# KimCard-r5.net
KiCad netlist of a schematic drawn in EAGLE
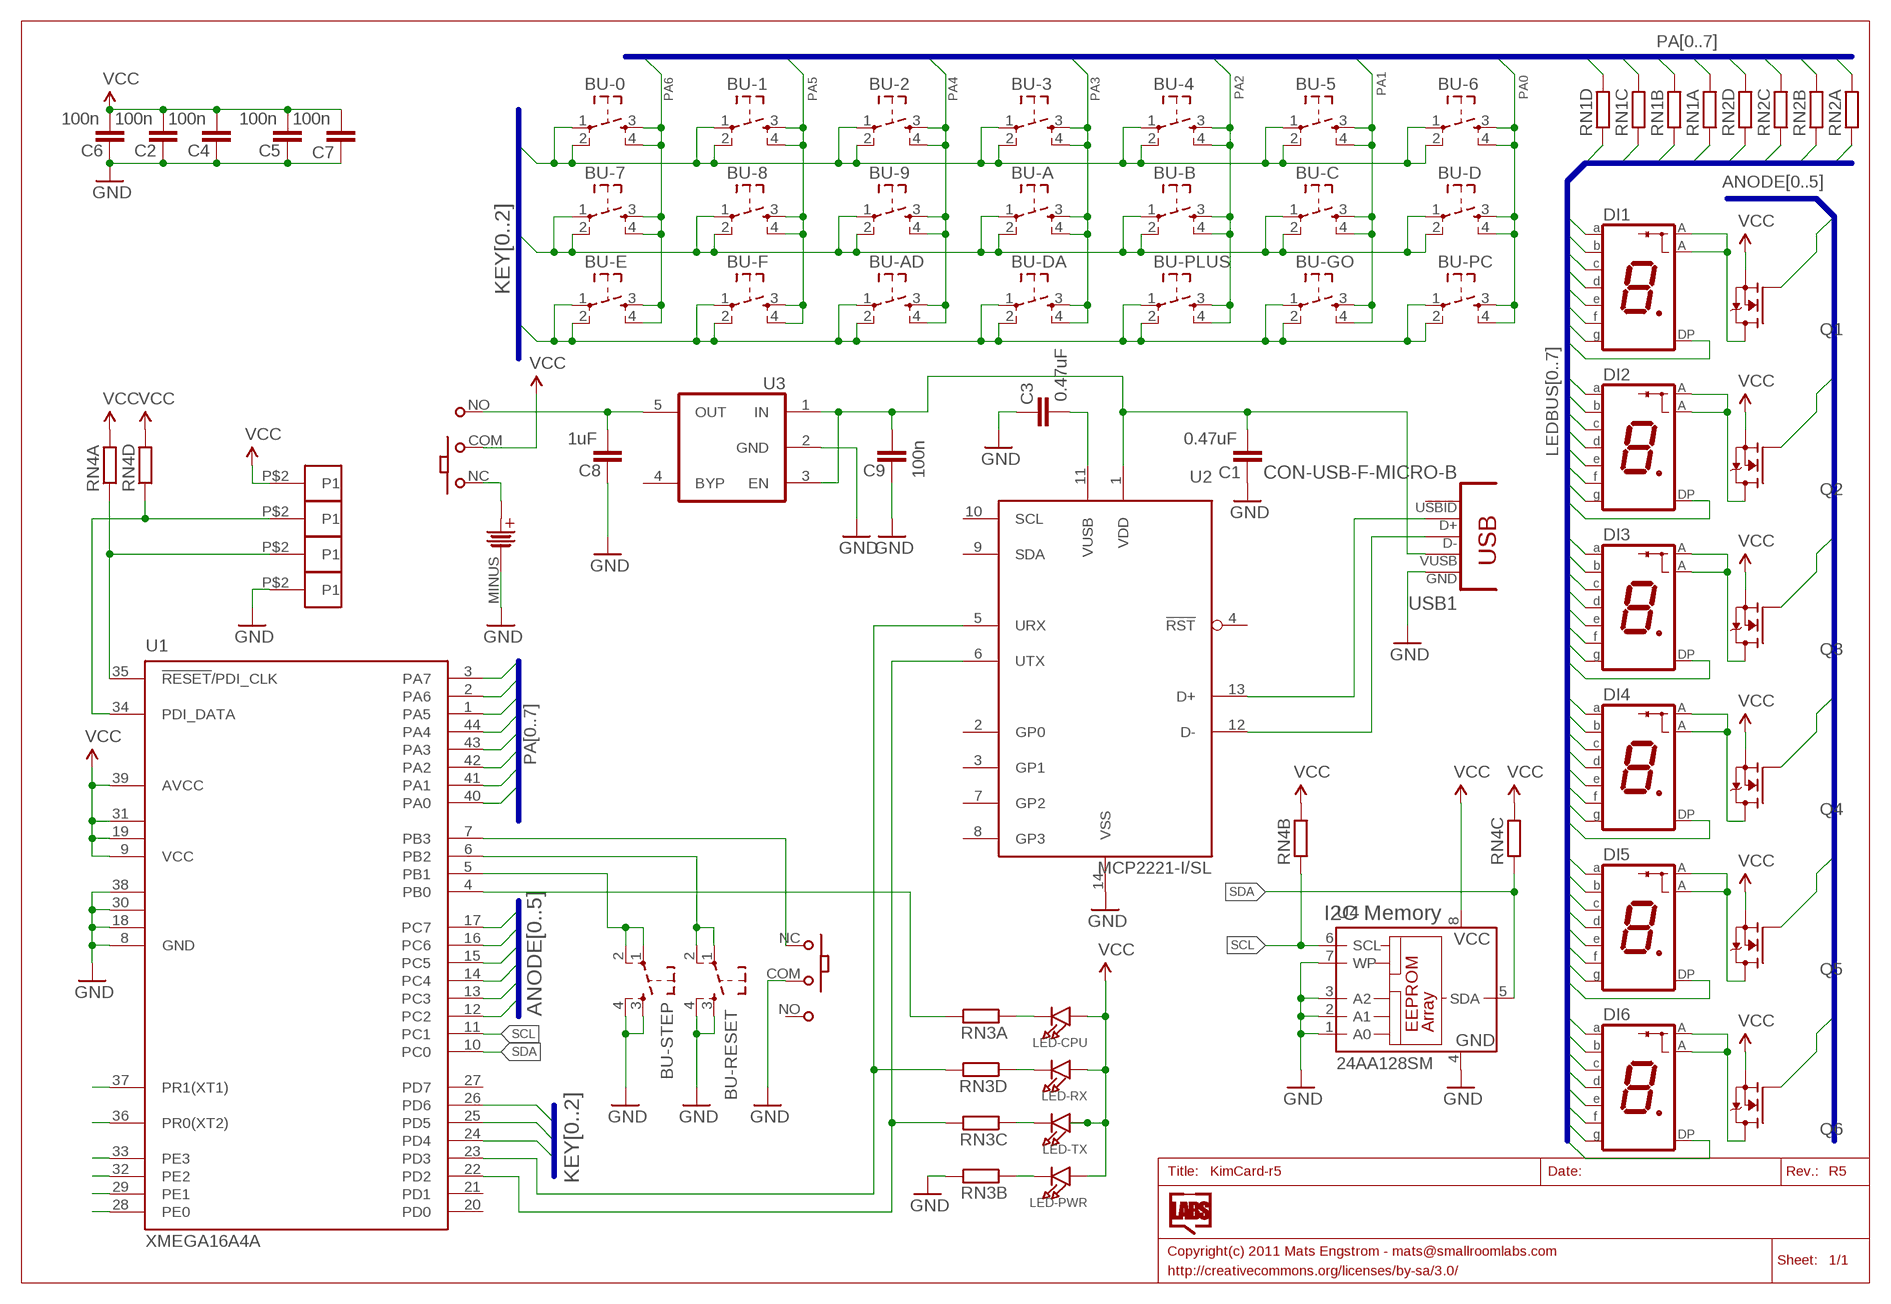
[diagram p0: schematic, sheet 1]

(export (version "E")
  (design (tool "Eeschema 10.0.6"))
  (components
    (comp (ref "BA1")
      (value "BATTERY-3V")
      (footprint "eagle-import:AAAX2")
      (libsource (lib "eagle-import") (part "BATTERY-3V"))
    )
    (comp (ref "BU-0")
      (value "SW_TACT_4P")
      (footprint "eagle-import:SW_TACT_SMALL")
      (libsource (lib "eagle-import") (part "SW_TACT_4P"))
    )
    (comp (ref "BU-1")
      (value "SW_TACT_4P")
      (footprint "eagle-import:SW_TACT_SMALL")
      (libsource (lib "eagle-import") (part "SW_TACT_4P"))
    )
    (comp (ref "BU-2")
      (value "SW_TACT_4P")
      (footprint "eagle-import:SW_TACT_SMALL")
      (libsource (lib "eagle-import") (part "SW_TACT_4P"))
    )
    (comp (ref "BU-3")
      (value "SW_TACT_4P")
      (footprint "eagle-import:SW_TACT_SMALL")
      (libsource (lib "eagle-import") (part "SW_TACT_4P"))
    )
    (comp (ref "BU-4")
      (value "SW_TACT_4P")
      (footprint "eagle-import:SW_TACT_SMALL")
      (libsource (lib "eagle-import") (part "SW_TACT_4P"))
    )
    (comp (ref "BU-5")
      (value "SW_TACT_4P")
      (footprint "eagle-import:SW_TACT_SMALL")
      (libsource (lib "eagle-import") (part "SW_TACT_4P"))
    )
    (comp (ref "BU-6")
      (value "SW_TACT_4P")
      (footprint "eagle-import:SW_TACT_SMALL")
      (libsource (lib "eagle-import") (part "SW_TACT_4P"))
    )
    (comp (ref "BU-7")
      (value "SW_TACT_4P")
      (footprint "eagle-import:SW_TACT_SMALL")
      (libsource (lib "eagle-import") (part "SW_TACT_4P"))
    )
    (comp (ref "BU-8")
      (value "SW_TACT_4P")
      (footprint "eagle-import:SW_TACT_SMALL")
      (libsource (lib "eagle-import") (part "SW_TACT_4P"))
    )
    (comp (ref "BU-9")
      (value "SW_TACT_4P")
      (footprint "eagle-import:SW_TACT_SMALL")
      (libsource (lib "eagle-import") (part "SW_TACT_4P"))
    )
    (comp (ref "BU-A")
      (value "SW_TACT_4P")
      (footprint "eagle-import:SW_TACT_SMALL")
      (libsource (lib "eagle-import") (part "SW_TACT_4P"))
    )
    (comp (ref "BU-AD")
      (value "SW_TACT_4P")
      (footprint "eagle-import:SW_TACT_SMALL")
      (libsource (lib "eagle-import") (part "SW_TACT_4P"))
    )
    (comp (ref "BU-B")
      (value "SW_TACT_4P")
      (footprint "eagle-import:SW_TACT_SMALL")
      (libsource (lib "eagle-import") (part "SW_TACT_4P"))
    )
    (comp (ref "BU-C")
      (value "SW_TACT_4P")
      (footprint "eagle-import:SW_TACT_SMALL")
      (libsource (lib "eagle-import") (part "SW_TACT_4P"))
    )
    (comp (ref "BU-D")
      (value "SW_TACT_4P")
      (footprint "eagle-import:SW_TACT_SMALL")
      (libsource (lib "eagle-import") (part "SW_TACT_4P"))
    )
    (comp (ref "BU-DA")
      (value "SW_TACT_4P")
      (footprint "eagle-import:SW_TACT_SMALL")
      (libsource (lib "eagle-import") (part "SW_TACT_4P"))
    )
    (comp (ref "BU-E")
      (value "SW_TACT_4P")
      (footprint "eagle-import:SW_TACT_SMALL")
      (libsource (lib "eagle-import") (part "SW_TACT_4P"))
    )
    (comp (ref "BU-F")
      (value "SW_TACT_4P")
      (footprint "eagle-import:SW_TACT_SMALL")
      (libsource (lib "eagle-import") (part "SW_TACT_4P"))
    )
    (comp (ref "BU-GO")
      (value "SW_TACT_4P")
      (footprint "eagle-import:SW_TACT_SMALL")
      (libsource (lib "eagle-import") (part "SW_TACT_4P"))
    )
    (comp (ref "BU-PC")
      (value "SW_TACT_4P")
      (footprint "eagle-import:SW_TACT_SMALL")
      (libsource (lib "eagle-import") (part "SW_TACT_4P"))
    )
    (comp (ref "BU-PLUS")
      (value "SW_TACT_4P")
      (footprint "eagle-import:SW_TACT_SMALL")
      (libsource (lib "eagle-import") (part "SW_TACT_4P"))
    )
    (comp (ref "BU-RESET")
      (value "SW_TACT_4P")
      (footprint "eagle-import:SW_TACT_SMALL")
      (libsource (lib "eagle-import") (part "SW_TACT_4P"))
    )
    (comp (ref "BU-STEP")
      (value "SW_TACT_4P")
      (footprint "eagle-import:SW_TACT_SMALL")
      (libsource (lib "eagle-import") (part "SW_TACT_4P"))
    )
    (comp (ref "C1")
      (value "0.47uF")
      (footprint "eagle-import:0805")
      (libsource (lib "eagle-import") (part "CAP0805"))
    )
    (comp (ref "C2")
      (value "100n")
      (footprint "eagle-import:0805")
      (libsource (lib "eagle-import") (part "CAP0805"))
    )
    (comp (ref "C3")
      (value "0.47uF")
      (footprint "eagle-import:0805")
      (libsource (lib "eagle-import") (part "CAP0805"))
    )
    (comp (ref "C4")
      (value "100n")
      (footprint "eagle-import:0805")
      (libsource (lib "eagle-import") (part "CAP0805"))
    )
    (comp (ref "C5")
      (value "100n")
      (footprint "eagle-import:0805")
      (libsource (lib "eagle-import") (part "CAP0805"))
    )
    (comp (ref "C6")
      (value "100n")
      (footprint "eagle-import:0805")
      (libsource (lib "eagle-import") (part "CAP0805"))
    )
    (comp (ref "C7")
      (value "100n")
      (footprint "eagle-import:0805")
      (libsource (lib "eagle-import") (part "CAP0805"))
    )
    (comp (ref "C8")
      (value "1uF")
      (footprint "eagle-import:0805")
      (libsource (lib "eagle-import") (part "CAP0805"))
    )
    (comp (ref "C9")
      (value "100n")
      (footprint "eagle-import:0805")
      (libsource (lib "eagle-import") (part "CAP0805"))
    )
    (comp (ref "DI1")
      (value "7SEG-CA2")
      (footprint "eagle-import:KCSA03")
      (libsource (lib "eagle-import") (part "7SEG-CA2"))
    )
    (comp (ref "DI2")
      (value "7SEG-CA2")
      (footprint "eagle-import:KCSA03")
      (libsource (lib "eagle-import") (part "7SEG-CA2"))
    )
    (comp (ref "DI3")
      (value "7SEG-CA2")
      (footprint "eagle-import:KCSA03")
      (libsource (lib "eagle-import") (part "7SEG-CA2"))
    )
    (comp (ref "DI4")
      (value "7SEG-CA2")
      (footprint "eagle-import:KCSA03")
      (libsource (lib "eagle-import") (part "7SEG-CA2"))
    )
    (comp (ref "DI5")
      (value "7SEG-CA2")
      (footprint "eagle-import:KCSA03")
      (libsource (lib "eagle-import") (part "7SEG-CA2"))
    )
    (comp (ref "DI6")
      (value "7SEG-CA2")
      (footprint "eagle-import:KCSA03")
      (libsource (lib "eagle-import") (part "7SEG-CA2"))
    )
    (comp (ref "LED-CPU")
      (value "LEDSMD0805")
      (footprint "eagle-import:CHIPLED_0805")
      (libsource (lib "eagle-import") (part "LEDSMD0805"))
    )
    (comp (ref "LED-PWR")
      (value "LEDSMD0805")
      (footprint "eagle-import:CHIPLED_0805")
      (libsource (lib "eagle-import") (part "LEDSMD0805"))
    )
    (comp (ref "LED-RX")
      (value "LEDSMD0805")
      (footprint "eagle-import:CHIPLED_0805")
      (libsource (lib "eagle-import") (part "LEDSMD0805"))
    )
    (comp (ref "LED-TX")
      (value "LEDSMD0805")
      (footprint "eagle-import:CHIPLED_0805")
      (libsource (lib "eagle-import") (part "LEDSMD0805"))
    )
    (comp (ref "PDI-CLK")
      (value "PAD-2X3")
      (footprint "eagle-import:PAD2X3")
      (libsource (lib "eagle-import") (part "PAD-2X3"))
    )
    (comp (ref "PDI-DATA")
      (value "PAD-2X3")
      (footprint "eagle-import:PAD2X3")
      (libsource (lib "eagle-import") (part "PAD-2X3"))
    )
    (comp (ref "PDI-GND")
      (value "PAD-2X3")
      (footprint "eagle-import:PAD2X3")
      (libsource (lib "eagle-import") (part "PAD-2X3"))
    )
    (comp (ref "PDI-VCC")
      (value "PAD-2X3")
      (footprint "eagle-import:PAD2X3")
      (libsource (lib "eagle-import") (part "PAD-2X3"))
    )
    (comp (ref "Q1")
      (value "TRANSISTOR_FET_BS170-SOT-23")
      (footprint "eagle-import:SOT-23")
      (libsource (lib "eagle-import") (part "TRANSISTOR_FET_BS170-SOT-23"))
    )
    (comp (ref "Q2")
      (value "TRANSISTOR_FET_BS170-SOT-23")
      (footprint "eagle-import:SOT-23")
      (libsource (lib "eagle-import") (part "TRANSISTOR_FET_BS170-SOT-23"))
    )
    (comp (ref "Q3")
      (value "TRANSISTOR_FET_BS170-SOT-23")
      (footprint "eagle-import:SOT-23")
      (libsource (lib "eagle-import") (part "TRANSISTOR_FET_BS170-SOT-23"))
    )
    (comp (ref "Q4")
      (value "TRANSISTOR_FET_BS170-SOT-23")
      (footprint "eagle-import:SOT-23")
      (libsource (lib "eagle-import") (part "TRANSISTOR_FET_BS170-SOT-23"))
    )
    (comp (ref "Q5")
      (value "TRANSISTOR_FET_BS170-SOT-23")
      (footprint "eagle-import:SOT-23")
      (libsource (lib "eagle-import") (part "TRANSISTOR_FET_BS170-SOT-23"))
    )
    (comp (ref "Q6")
      (value "TRANSISTOR_FET_BS170-SOT-23")
      (footprint "eagle-import:SOT-23")
      (libsource (lib "eagle-import") (part "TRANSISTOR_FET_BS170-SOT-23"))
    )
    (comp (ref "RN1")
      (value "RESISTOR_ARRAY_4")
      (footprint "eagle-import:RN8P-4R-CRA06S")
      (libsource (lib "eagle-import") (part "RESISTOR_ARRAY_4"))
    )
    (comp (ref "RN2")
      (value "RESISTOR_ARRAY_4")
      (footprint "eagle-import:RN8P-4R-CRA06S")
      (libsource (lib "eagle-import") (part "RESISTOR_ARRAY_4"))
    )
    (comp (ref "RN3")
      (value "RESISTOR_ARRAY_4")
      (footprint "eagle-import:RN8P-4R-CRA06S")
      (libsource (lib "eagle-import") (part "RESISTOR_ARRAY_4"))
    )
    (comp (ref "RN4")
      (value "RESISTOR_ARRAY_4")
      (footprint "eagle-import:RN8P-4R-CRA06S")
      (libsource (lib "eagle-import") (part "RESISTOR_ARRAY_4"))
    )
    (comp (ref "U$1")
      (value "SLIDESWITCHPCM12SMTR")
      (footprint "eagle-import:PCM12SMTR")
      (libsource (lib "eagle-import") (part "SLIDESWITCHPCM12SMTR"))
    )
    (comp (ref "U$2")
      (value "SLIDESWITCHPCM12SMTR")
      (footprint "eagle-import:PCM12SMTR")
      (libsource (lib "eagle-import") (part "SLIDESWITCHPCM12SMTR"))
    )
    (comp (ref "U1")
      (value "XMEGA16A4A")
      (footprint "eagle-import:TQFP44")
      (libsource (lib "eagle-import") (part "XMEGA16A4A"))
    )
    (comp (ref "U2")
      (value "MCP2221-I/SL")
      (footprint "eagle-import:SOIC14")
      (libsource (lib "eagle-import") (part "MCP2221-I/SL"))
    )
    (comp (ref "U3")
      (value "VREG_5PINS-SOT-23-5")
      (footprint "eagle-import:SOT-23-5")
      (libsource (lib "eagle-import") (part "VREG_5PINS-SOT-23-5"))
    )
    (comp (ref "U4")
      (value "24AA128SM")
      (footprint "eagle-import:SO-08M")
      (fields (field (name "MF") "MICROCHIP") (field (name "MPN") "24AA128-I/MS"))
      (libsource (lib "eagle-import") (part "24SMAA128"))
    )
    (comp (ref "USB1")
      (value "CON-USB-F-MICRO-B")
      (footprint "eagle-import:CONN_USB_MICRO-B")
      (libsource (lib "eagle-import") (part "CON-USB-F-MICRO-B"))
    )
  )
  (nets
    (net (code "11") (name "/KEYROW0") (class "Default")
      (node (ref "BU-0") (pin "1") (pinfunction "1_1") (pintype "passive"))
      (node (ref "BU-0") (pin "2") (pinfunction "2_2") (pintype "passive"))
      (node (ref "BU-1") (pin "1") (pinfunction "1_1") (pintype "passive"))
      (node (ref "BU-1") (pin "2") (pinfunction "2_2") (pintype "passive"))
      (node (ref "BU-2") (pin "1") (pinfunction "1_1") (pintype "passive"))
      (node (ref "BU-2") (pin "2") (pinfunction "2_2") (pintype "passive"))
      (node (ref "BU-3") (pin "1") (pinfunction "1_1") (pintype "passive"))
      (node (ref "BU-3") (pin "2") (pinfunction "2_2") (pintype "passive"))
      (node (ref "BU-4") (pin "1") (pinfunction "1_1") (pintype "passive"))
      (node (ref "BU-4") (pin "2") (pinfunction "2_2") (pintype "passive"))
      (node (ref "BU-5") (pin "1") (pinfunction "1_1") (pintype "passive"))
      (node (ref "BU-5") (pin "2") (pinfunction "2_2") (pintype "passive"))
      (node (ref "BU-6") (pin "1") (pinfunction "1_1") (pintype "passive"))
      (node (ref "BU-6") (pin "2") (pinfunction "2_2") (pintype "passive"))
      (node (ref "U1") (pin "24") (pinfunction "PD4_24") (pintype "bidirectional"))
    )
    (net (code "12") (name "/KEYROW1") (class "Default")
      (node (ref "BU-7") (pin "1") (pinfunction "1_1") (pintype "passive"))
      (node (ref "BU-7") (pin "2") (pinfunction "2_2") (pintype "passive"))
      (node (ref "BU-8") (pin "1") (pinfunction "1_1") (pintype "passive"))
      (node (ref "BU-8") (pin "2") (pinfunction "2_2") (pintype "passive"))
      (node (ref "BU-9") (pin "1") (pinfunction "1_1") (pintype "passive"))
      (node (ref "BU-9") (pin "2") (pinfunction "2_2") (pintype "passive"))
      (node (ref "BU-A") (pin "1") (pinfunction "1_1") (pintype "passive"))
      (node (ref "BU-A") (pin "2") (pinfunction "2_2") (pintype "passive"))
      (node (ref "BU-B") (pin "1") (pinfunction "1_1") (pintype "passive"))
      (node (ref "BU-B") (pin "2") (pinfunction "2_2") (pintype "passive"))
      (node (ref "BU-C") (pin "1") (pinfunction "1_1") (pintype "passive"))
      (node (ref "BU-C") (pin "2") (pinfunction "2_2") (pintype "passive"))
      (node (ref "BU-D") (pin "1") (pinfunction "1_1") (pintype "passive"))
      (node (ref "BU-D") (pin "2") (pinfunction "2_2") (pintype "passive"))
      (node (ref "U1") (pin "25") (pinfunction "PD5_25") (pintype "bidirectional"))
    )
    (net (code "13") (name "/KEYROW2") (class "Default")
      (node (ref "BU-AD") (pin "1") (pinfunction "1_1") (pintype "passive"))
      (node (ref "BU-AD") (pin "2") (pinfunction "2_2") (pintype "passive"))
      (node (ref "BU-DA") (pin "1") (pinfunction "1_1") (pintype "passive"))
      (node (ref "BU-DA") (pin "2") (pinfunction "2_2") (pintype "passive"))
      (node (ref "BU-E") (pin "1") (pinfunction "1_1") (pintype "passive"))
      (node (ref "BU-E") (pin "2") (pinfunction "2_2") (pintype "passive"))
      (node (ref "BU-F") (pin "1") (pinfunction "1_1") (pintype "passive"))
      (node (ref "BU-F") (pin "2") (pinfunction "2_2") (pintype "passive"))
      (node (ref "BU-GO") (pin "1") (pinfunction "1_1") (pintype "passive"))
      (node (ref "BU-GO") (pin "2") (pinfunction "2_2") (pintype "passive"))
      (node (ref "BU-PC") (pin "1") (pinfunction "1_1") (pintype "passive"))
      (node (ref "BU-PC") (pin "2") (pinfunction "2_2") (pintype "passive"))
      (node (ref "BU-PLUS") (pin "1") (pinfunction "1_1") (pintype "passive"))
      (node (ref "BU-PLUS") (pin "2") (pinfunction "2_2") (pintype "passive"))
      (node (ref "U1") (pin "26") (pinfunction "PD6_26") (pintype "bidirectional"))
    )
    (net (code "15") (name "/LEDBUS0") (class "Default")
      (node (ref "DI1") (pin "P$7") (pinfunction "A_P$7") (pintype "passive"))
      (node (ref "DI2") (pin "P$7") (pinfunction "A_P$7") (pintype "passive"))
      (node (ref "DI3") (pin "P$7") (pinfunction "A_P$7") (pintype "passive"))
      (node (ref "DI4") (pin "P$7") (pinfunction "A_P$7") (pintype "passive"))
      (node (ref "DI5") (pin "P$7") (pinfunction "A_P$7") (pintype "passive"))
      (node (ref "DI6") (pin "P$7") (pinfunction "A_P$7") (pintype "passive"))
      (node (ref "RN2") (pin "1") (pinfunction "1_1") (pintype "passive"))
    )
    (net (code "16") (name "/LEDBUS1") (class "Default")
      (node (ref "DI1") (pin "P$6") (pinfunction "B_P$6") (pintype "passive"))
      (node (ref "DI2") (pin "P$6") (pinfunction "B_P$6") (pintype "passive"))
      (node (ref "DI3") (pin "P$6") (pinfunction "B_P$6") (pintype "passive"))
      (node (ref "DI4") (pin "P$6") (pinfunction "B_P$6") (pintype "passive"))
      (node (ref "DI5") (pin "P$6") (pinfunction "B_P$6") (pintype "passive"))
      (node (ref "DI6") (pin "P$6") (pinfunction "B_P$6") (pintype "passive"))
      (node (ref "RN2") (pin "2") (pinfunction "1_2") (pintype "passive"))
    )
    (net (code "17") (name "/LEDBUS2") (class "Default")
      (node (ref "DI1") (pin "P$4") (pinfunction "C_P$4") (pintype "passive"))
      (node (ref "DI2") (pin "P$4") (pinfunction "C_P$4") (pintype "passive"))
      (node (ref "DI3") (pin "P$4") (pinfunction "C_P$4") (pintype "passive"))
      (node (ref "DI4") (pin "P$4") (pinfunction "C_P$4") (pintype "passive"))
      (node (ref "DI5") (pin "P$4") (pinfunction "C_P$4") (pintype "passive"))
      (node (ref "DI6") (pin "P$4") (pinfunction "C_P$4") (pintype "passive"))
      (node (ref "RN2") (pin "3") (pinfunction "1_3") (pintype "passive"))
    )
    (net (code "18") (name "/LEDBUS3") (class "Default")
      (node (ref "DI1") (pin "P$2") (pinfunction "D_P$2") (pintype "passive"))
      (node (ref "DI2") (pin "P$2") (pinfunction "D_P$2") (pintype "passive"))
      (node (ref "DI3") (pin "P$2") (pinfunction "D_P$2") (pintype "passive"))
      (node (ref "DI4") (pin "P$2") (pinfunction "D_P$2") (pintype "passive"))
      (node (ref "DI5") (pin "P$2") (pinfunction "D_P$2") (pintype "passive"))
      (node (ref "DI6") (pin "P$2") (pinfunction "D_P$2") (pintype "passive"))
      (node (ref "RN2") (pin "4") (pinfunction "1_4") (pintype "passive"))
    )
    (net (code "19") (name "/LEDBUS4") (class "Default")
      (node (ref "DI1") (pin "P$1") (pinfunction "E_P$1") (pintype "passive"))
      (node (ref "DI2") (pin "P$1") (pinfunction "E_P$1") (pintype "passive"))
      (node (ref "DI3") (pin "P$1") (pinfunction "E_P$1") (pintype "passive"))
      (node (ref "DI4") (pin "P$1") (pinfunction "E_P$1") (pintype "passive"))
      (node (ref "DI5") (pin "P$1") (pinfunction "E_P$1") (pintype "passive"))
      (node (ref "DI6") (pin "P$1") (pinfunction "E_P$1") (pintype "passive"))
      (node (ref "RN1") (pin "1") (pinfunction "1_1") (pintype "passive"))
    )
    (net (code "20") (name "/LEDBUS5") (class "Default")
      (node (ref "DI1") (pin "P$9") (pinfunction "F_P$9") (pintype "passive"))
      (node (ref "DI2") (pin "P$9") (pinfunction "F_P$9") (pintype "passive"))
      (node (ref "DI3") (pin "P$9") (pinfunction "F_P$9") (pintype "passive"))
      (node (ref "DI4") (pin "P$9") (pinfunction "F_P$9") (pintype "passive"))
      (node (ref "DI5") (pin "P$9") (pinfunction "F_P$9") (pintype "passive"))
      (node (ref "DI6") (pin "P$9") (pinfunction "F_P$9") (pintype "passive"))
      (node (ref "RN1") (pin "2") (pinfunction "1_2") (pintype "passive"))
    )
    (net (code "21") (name "/LEDBUS6") (class "Default")
      (node (ref "DI1") (pin "P$10") (pinfunction "G_P$10") (pintype "passive"))
      (node (ref "DI2") (pin "P$10") (pinfunction "G_P$10") (pintype "passive"))
      (node (ref "DI3") (pin "P$10") (pinfunction "G_P$10") (pintype "passive"))
      (node (ref "DI4") (pin "P$10") (pinfunction "G_P$10") (pintype "passive"))
      (node (ref "DI5") (pin "P$10") (pinfunction "G_P$10") (pintype "passive"))
      (node (ref "DI6") (pin "P$10") (pinfunction "G_P$10") (pintype "passive"))
      (node (ref "RN1") (pin "3") (pinfunction "1_3") (pintype "passive"))
    )
    (net (code "22") (name "/LEDBUS7") (class "Default")
      (node (ref "DI1") (pin "P$5") (pinfunction "DP_P$5") (pintype "passive"))
      (node (ref "DI2") (pin "P$5") (pinfunction "DP_P$5") (pintype "passive"))
      (node (ref "DI3") (pin "P$5") (pinfunction "DP_P$5") (pintype "passive"))
      (node (ref "DI4") (pin "P$5") (pinfunction "DP_P$5") (pintype "passive"))
      (node (ref "DI5") (pin "P$5") (pinfunction "DP_P$5") (pintype "passive"))
      (node (ref "DI6") (pin "P$5") (pinfunction "DP_P$5") (pintype "passive"))
      (node (ref "RN1") (pin "4") (pinfunction "1_4") (pintype "passive"))
    )
    (net (code "24") (name "/LEDCA0") (class "Default")
      (node (ref "Q1") (pin "1") (pinfunction "G_1") (pintype "passive"))
      (node (ref "U1") (pin "12") (pinfunction "PC2_12") (pintype "bidirectional"))
    )
    (net (code "25") (name "/LEDCA1") (class "Default")
      (node (ref "Q2") (pin "1") (pinfunction "G_1") (pintype "passive"))
      (node (ref "U1") (pin "13") (pinfunction "PC3_13") (pintype "bidirectional"))
    )
    (net (code "26") (name "/LEDCA2") (class "Default")
      (node (ref "Q3") (pin "1") (pinfunction "G_1") (pintype "passive"))
      (node (ref "U1") (pin "14") (pinfunction "PC4_14") (pintype "bidirectional"))
    )
    (net (code "27") (name "/LEDCA3") (class "Default")
      (node (ref "Q4") (pin "1") (pinfunction "G_1") (pintype "passive"))
      (node (ref "U1") (pin "15") (pinfunction "PC5_15") (pintype "bidirectional"))
    )
    (net (code "28") (name "/LEDCA4") (class "Default")
      (node (ref "Q5") (pin "1") (pinfunction "G_1") (pintype "passive"))
      (node (ref "U1") (pin "16") (pinfunction "PC6_16") (pintype "bidirectional"))
    )
    (net (code "29") (name "/LEDCA5") (class "Default")
      (node (ref "Q6") (pin "1") (pinfunction "G_1") (pintype "passive"))
      (node (ref "U1") (pin "17") (pinfunction "PC7_17") (pintype "bidirectional"))
    )
    (net (code "30") (name "/PA0") (class "Default")
      (node (ref "BU-6") (pin "3") (pinfunction "3_3") (pintype "passive"))
      (node (ref "BU-6") (pin "4") (pinfunction "4_4") (pintype "passive"))
      (node (ref "BU-D") (pin "3") (pinfunction "3_3") (pintype "passive"))
      (node (ref "BU-D") (pin "4") (pinfunction "4_4") (pintype "passive"))
      (node (ref "BU-PC") (pin "3") (pinfunction "3_3") (pintype "passive"))
      (node (ref "BU-PC") (pin "4") (pinfunction "4_4") (pintype "passive"))
      (node (ref "RN2") (pin "8") (pinfunction "2_8") (pintype "passive"))
      (node (ref "U1") (pin "40") (pinfunction "PA0_40") (pintype "bidirectional"))
    )
    (net (code "31") (name "/PA1") (class "Default")
      (node (ref "BU-5") (pin "3") (pinfunction "3_3") (pintype "passive"))
      (node (ref "BU-5") (pin "4") (pinfunction "4_4") (pintype "passive"))
      (node (ref "BU-C") (pin "3") (pinfunction "3_3") (pintype "passive"))
      (node (ref "BU-C") (pin "4") (pinfunction "4_4") (pintype "passive"))
      (node (ref "BU-GO") (pin "3") (pinfunction "3_3") (pintype "passive"))
      (node (ref "BU-GO") (pin "4") (pinfunction "4_4") (pintype "passive"))
      (node (ref "RN2") (pin "7") (pinfunction "2_7") (pintype "passive"))
      (node (ref "U1") (pin "41") (pinfunction "PA1_41") (pintype "bidirectional"))
    )
    (net (code "32") (name "/PA2") (class "Default")
      (node (ref "BU-4") (pin "3") (pinfunction "3_3") (pintype "passive"))
      (node (ref "BU-4") (pin "4") (pinfunction "4_4") (pintype "passive"))
      (node (ref "BU-B") (pin "3") (pinfunction "3_3") (pintype "passive"))
      (node (ref "BU-B") (pin "4") (pinfunction "4_4") (pintype "passive"))
      (node (ref "BU-PLUS") (pin "3") (pinfunction "3_3") (pintype "passive"))
      (node (ref "BU-PLUS") (pin "4") (pinfunction "4_4") (pintype "passive"))
      (node (ref "RN2") (pin "6") (pinfunction "2_6") (pintype "passive"))
      (node (ref "U1") (pin "42") (pinfunction "PA2_42") (pintype "bidirectional"))
    )
    (net (code "33") (name "/PA3") (class "Default")
      (node (ref "BU-3") (pin "3") (pinfunction "3_3") (pintype "passive"))
      (node (ref "BU-3") (pin "4") (pinfunction "4_4") (pintype "passive"))
      (node (ref "BU-A") (pin "3") (pinfunction "3_3") (pintype "passive"))
      (node (ref "BU-A") (pin "4") (pinfunction "4_4") (pintype "passive"))
      (node (ref "BU-DA") (pin "3") (pinfunction "3_3") (pintype "passive"))
      (node (ref "BU-DA") (pin "4") (pinfunction "4_4") (pintype "passive"))
      (node (ref "RN2") (pin "5") (pinfunction "2_5") (pintype "passive"))
      (node (ref "U1") (pin "43") (pinfunction "PA3_43") (pintype "bidirectional"))
    )
    (net (code "34") (name "/PA4") (class "Default")
      (node (ref "BU-2") (pin "3") (pinfunction "3_3") (pintype "passive"))
      (node (ref "BU-2") (pin "4") (pinfunction "4_4") (pintype "passive"))
      (node (ref "BU-9") (pin "3") (pinfunction "3_3") (pintype "passive"))
      (node (ref "BU-9") (pin "4") (pinfunction "4_4") (pintype "passive"))
      (node (ref "BU-AD") (pin "3") (pinfunction "3_3") (pintype "passive"))
      (node (ref "BU-AD") (pin "4") (pinfunction "4_4") (pintype "passive"))
      (node (ref "RN1") (pin "8") (pinfunction "2_8") (pintype "passive"))
      (node (ref "U1") (pin "44") (pinfunction "PA4_44") (pintype "bidirectional"))
    )
    (net (code "35") (name "/PA5") (class "Default")
      (node (ref "BU-1") (pin "3") (pinfunction "3_3") (pintype "passive"))
      (node (ref "BU-1") (pin "4") (pinfunction "4_4") (pintype "passive"))
      (node (ref "BU-8") (pin "3") (pinfunction "3_3") (pintype "passive"))
      (node (ref "BU-8") (pin "4") (pinfunction "4_4") (pintype "passive"))
      (node (ref "BU-F") (pin "3") (pinfunction "3_3") (pintype "passive"))
      (node (ref "BU-F") (pin "4") (pinfunction "4_4") (pintype "passive"))
      (node (ref "RN1") (pin "7") (pinfunction "2_7") (pintype "passive"))
      (node (ref "U1") (pin "1") (pinfunction "PA5_1") (pintype "bidirectional"))
    )
    (net (code "36") (name "/PA6") (class "Default")
      (node (ref "BU-0") (pin "3") (pinfunction "3_3") (pintype "passive"))
      (node (ref "BU-0") (pin "4") (pinfunction "4_4") (pintype "passive"))
      (node (ref "BU-7") (pin "3") (pinfunction "3_3") (pintype "passive"))
      (node (ref "BU-7") (pin "4") (pinfunction "4_4") (pintype "passive"))
      (node (ref "BU-E") (pin "3") (pinfunction "3_3") (pintype "passive"))
      (node (ref "BU-E") (pin "4") (pinfunction "4_4") (pintype "passive"))
      (node (ref "RN1") (pin "6") (pinfunction "2_6") (pintype "passive"))
      (node (ref "U1") (pin "2") (pinfunction "PA6_2") (pintype "bidirectional"))
    )
    (net (code "37") (name "/PA7") (class "Default")
      (node (ref "RN1") (pin "5") (pinfunction "2_5") (pintype "passive"))
      (node (ref "U1") (pin "3") (pinfunction "PA7_3") (pintype "bidirectional"))
    )
    (net (code "39") (name "GND") (class "Default")
      (node (ref "BA1") (pin "MINUS") (pinfunction "MINUS_MINUS") (pintype "power_in"))
      (node (ref "BU-RESET") (pin "3") (pinfunction "3_3") (pintype "passive"))
      (node (ref "BU-RESET") (pin "4") (pinfunction "4_4") (pintype "passive"))
      (node (ref "BU-STEP") (pin "3") (pinfunction "3_3") (pintype "passive"))
      (node (ref "BU-STEP") (pin "4") (pinfunction "4_4") (pintype "passive"))
      (node (ref "C1") (pin "1") (pinfunction "1_1") (pintype "passive"))
      (node (ref "C2") (pin "1") (pinfunction "1_1") (pintype "passive"))
      (node (ref "C3") (pin "1") (pinfunction "1_1") (pintype "passive"))
      (node (ref "C4") (pin "1") (pinfunction "1_1") (pintype "passive"))
      (node (ref "C5") (pin "1") (pinfunction "1_1") (pintype "passive"))
      (node (ref "C6") (pin "1") (pinfunction "1_1") (pintype "passive"))
      (node (ref "C7") (pin "1") (pinfunction "1_1") (pintype "passive"))
      (node (ref "C8") (pin "1") (pinfunction "1_1") (pintype "passive"))
      (node (ref "C9") (pin "1") (pinfunction "1_1") (pintype "passive"))
      (node (ref "PDI-GND") (pin "P$2") (pinfunction "P1_P$2") (pintype "bidirectional"))
      (node (ref "RN3") (pin "7") (pinfunction "2_7") (pintype "passive"))
      (node (ref "U$2") (pin "COM") (pinfunction "COM_COM") (pintype "bidirectional"))
      (node (ref "U1") (pin "18") (pinfunction "GND1_18") (pintype "power_in"))
      (node (ref "U1") (pin "30") (pinfunction "GND2_30") (pintype "power_in"))
      (node (ref "U1") (pin "38") (pinfunction "GND3_38") (pintype "power_in"))
      (node (ref "U1") (pin "8") (pinfunction "GND_8") (pintype "power_in"))
      (node (ref "U2") (pin "14") (pinfunction "VSS_14") (pintype "power_in"))
      (node (ref "U3") (pin "2") (pinfunction "GND_2") (pintype "bidirectional"))
      (node (ref "U4") (pin "1") (pinfunction "A0_1") (pintype "input"))
      (node (ref "U4") (pin "2") (pinfunction "A1_2") (pintype "input"))
      (node (ref "U4") (pin "3") (pinfunction "A2_3") (pintype "input"))
      (node (ref "U4") (pin "4") (pinfunction "GND_4") (pintype "power_in"))
      (node (ref "U4") (pin "7") (pinfunction "WP_7") (pintype "input"))
      (node (ref "USB1") (pin "P5") (pinfunction "GND_P5") (pintype "bidirectional"))
    )
    (net (code "40") (name "Net-(BA1-PadPLUS)") (class "Default")
      (node (ref "BA1") (pin "PLUS") (pinfunction "PLUS_PLUS") (pintype "power_in"))
      (node (ref "U$1") (pin "NC") (pinfunction "NC_NC") (pintype "passive"))
    )
    (net (code "41") (name "Net-(LED-CPU-PadC)") (class "Default")
      (node (ref "LED-CPU") (pin "C") (pinfunction "C_C") (pintype "passive"))
      (node (ref "RN3") (pin "1") (pinfunction "1_1") (pintype "passive"))
    )
    (net (code "42") (name "Net-(PDI-CLK-P1)") (class "Default")
      (node (ref "PDI-CLK") (pin "P$2") (pinfunction "P1_P$2") (pintype "bidirectional"))
      (node (ref "RN4") (pin "1") (pinfunction "1_1") (pintype "passive"))
      (node (ref "U1") (pin "35") (pinfunction "~{RESET}/PDI_CLK_35") (pintype "bidirectional"))
    )
    (net (code "43") (name "Net-(PDI-DATA-P1)") (class "Default")
      (node (ref "PDI-DATA") (pin "P$2") (pinfunction "P1_P$2") (pintype "bidirectional"))
      (node (ref "RN4") (pin "4") (pinfunction "1_4") (pintype "passive"))
      (node (ref "U1") (pin "34") (pinfunction "PDI_DATA_34") (pintype "bidirectional"))
    )
    (net (code "44") (name "Net-(Q1-D)") (class "Default")
      (node (ref "DI1") (pin "P$3") (pinfunction "A_P$3") (pintype "passive"))
      (node (ref "DI1") (pin "P$8") (pinfunction "A_P$8") (pintype "passive"))
      (node (ref "Q1") (pin "3") (pinfunction "D_3") (pintype "passive"))
    )
    (net (code "45") (name "Net-(Q2-D)") (class "Default")
      (node (ref "DI2") (pin "P$3") (pinfunction "A_P$3") (pintype "passive"))
      (node (ref "DI2") (pin "P$8") (pinfunction "A_P$8") (pintype "passive"))
      (node (ref "Q2") (pin "3") (pinfunction "D_3") (pintype "passive"))
    )
    (net (code "46") (name "Net-(Q3-D)") (class "Default")
      (node (ref "DI3") (pin "P$3") (pinfunction "A_P$3") (pintype "passive"))
      (node (ref "DI3") (pin "P$8") (pinfunction "A_P$8") (pintype "passive"))
      (node (ref "Q3") (pin "3") (pinfunction "D_3") (pintype "passive"))
    )
    (net (code "47") (name "Net-(Q4-D)") (class "Default")
      (node (ref "DI4") (pin "P$3") (pinfunction "A_P$3") (pintype "passive"))
      (node (ref "DI4") (pin "P$8") (pinfunction "A_P$8") (pintype "passive"))
      (node (ref "Q4") (pin "3") (pinfunction "D_3") (pintype "passive"))
    )
    (net (code "48") (name "Net-(Q5-D)") (class "Default")
      (node (ref "DI5") (pin "P$3") (pinfunction "A_P$3") (pintype "passive"))
      (node (ref "DI5") (pin "P$8") (pinfunction "A_P$8") (pintype "passive"))
      (node (ref "Q5") (pin "3") (pinfunction "D_3") (pintype "passive"))
    )
    (net (code "49") (name "Net-(Q6-D)") (class "Default")
      (node (ref "DI6") (pin "P$3") (pinfunction "A_P$3") (pintype "passive"))
      (node (ref "DI6") (pin "P$8") (pinfunction "A_P$8") (pintype "passive"))
      (node (ref "Q6") (pin "3") (pinfunction "D_3") (pintype "passive"))
    )
    (net (code "50") (name "Net-(RN3A-2)") (class "Default")
      (node (ref "RN3") (pin "8") (pinfunction "2_8") (pintype "passive"))
      (node (ref "U1") (pin "4") (pinfunction "PB0_4") (pintype "bidirectional"))
    )
    (net (code "51") (name "Net-(RN3B-1)") (class "Default")
      (node (ref "LED-PWR") (pin "C") (pinfunction "C_C") (pintype "passive"))
      (node (ref "RN3") (pin "2") (pinfunction "1_2") (pintype "passive"))
    )
    (net (code "52") (name "Net-(RN3C-1)") (class "Default")
      (node (ref "LED-TX") (pin "C") (pinfunction "C_C") (pintype "passive"))
      (node (ref "RN3") (pin "3") (pinfunction "1_3") (pintype "passive"))
    )
    (net (code "53") (name "Net-(RN3C-2)") (class "Default")
      (node (ref "RN3") (pin "6") (pinfunction "2_6") (pintype "passive"))
      (node (ref "U1") (pin "22") (pinfunction "PD2_22") (pintype "bidirectional"))
      (node (ref "U2") (pin "6") (pinfunction "UTX_6") (pintype "output"))
    )
    (net (code "54") (name "Net-(RN3D-1)") (class "Default")
      (node (ref "LED-RX") (pin "C") (pinfunction "C_C") (pintype "passive"))
      (node (ref "RN3") (pin "4") (pinfunction "1_4") (pintype "passive"))
    )
    (net (code "55") (name "Net-(RN3D-2)") (class "Default")
      (node (ref "RN3") (pin "5") (pinfunction "2_5") (pintype "passive"))
      (node (ref "U1") (pin "23") (pinfunction "PD3_23") (pintype "bidirectional"))
      (node (ref "U2") (pin "5") (pinfunction "URX_5") (pintype "input"))
    )
    (net (code "56") (name "Net-(U1-PB1)") (class "Default")
      (node (ref "BU-STEP") (pin "1") (pinfunction "1_1") (pintype "passive"))
      (node (ref "BU-STEP") (pin "2") (pinfunction "2_2") (pintype "passive"))
      (node (ref "U1") (pin "5") (pinfunction "PB1_5") (pintype "bidirectional"))
    )
    (net (code "57") (name "Net-(U1-PB2)") (class "Default")
      (node (ref "BU-RESET") (pin "1") (pinfunction "1_1") (pintype "passive"))
      (node (ref "BU-RESET") (pin "2") (pinfunction "2_2") (pintype "passive"))
      (node (ref "U1") (pin "6") (pinfunction "PB2_6") (pintype "bidirectional"))
    )
    (net (code "58") (name "Net-(U1-PB3)") (class "Default")
      (node (ref "U$2") (pin "NC") (pinfunction "NC_NC") (pintype "passive"))
      (node (ref "U1") (pin "7") (pinfunction "PB3_7") (pintype "bidirectional"))
    )
    (net (code "59") (name "Net-(U2-D+)") (class "Default")
      (node (ref "U2") (pin "13") (pinfunction "D+_13") (pintype "bidirectional"))
      (node (ref "USB1") (pin "P3") (pinfunction "D+_P3") (pintype "bidirectional"))
    )
    (net (code "60") (name "Net-(U2-D-)") (class "Default")
      (node (ref "U2") (pin "12") (pinfunction "D-_12") (pintype "bidirectional"))
      (node (ref "USB1") (pin "P2") (pinfunction "D-_P2") (pintype "bidirectional"))
    )
    (net (code "61") (name "Net-(U2-VDD)") (class "Default")
      (node (ref "C1") (pin "2") (pinfunction "2_2") (pintype "passive"))
      (node (ref "C9") (pin "2") (pinfunction "2_2") (pintype "passive"))
      (node (ref "U2") (pin "1") (pinfunction "VDD_1") (pintype "power_in"))
      (node (ref "U3") (pin "1") (pinfunction "IN_1") (pintype "bidirectional"))
      (node (ref "U3") (pin "3") (pinfunction "EN_3") (pintype "bidirectional"))
      (node (ref "USB1") (pin "P1") (pinfunction "VUSB_P1") (pintype "bidirectional"))
    )
    (net (code "62") (name "Net-(U2-VUSB)") (class "Default")
      (node (ref "C3") (pin "2") (pinfunction "2_2") (pintype "passive"))
      (node (ref "U2") (pin "11") (pinfunction "VUSB_11") (pintype "power_in"))
    )
    (net (code "63") (name "Net-(U3-OUT)") (class "Default")
      (node (ref "C8") (pin "2") (pinfunction "2_2") (pintype "passive"))
      (node (ref "U$1") (pin "NO") (pinfunction "NO_NO") (pintype "passive"))
      (node (ref "U3") (pin "5") (pinfunction "OUT_5") (pintype "bidirectional"))
    )
    (net (code "64") (name "SCL") (class "Default")
      (node (ref "RN4") (pin "2") (pinfunction "1_2") (pintype "passive"))
      (node (ref "U1") (pin "11") (pinfunction "PC1_11") (pintype "bidirectional"))
      (node (ref "U4") (pin "6") (pinfunction "SCL_6") (pintype "input"))
    )
    (net (code "65") (name "SDA") (class "Default")
      (node (ref "RN4") (pin "3") (pinfunction "1_3") (pintype "passive"))
      (node (ref "U1") (pin "10") (pinfunction "PC0_10") (pintype "bidirectional"))
      (node (ref "U4") (pin "5") (pinfunction "SDA_5") (pintype "bidirectional"))
    )
    (net (code "66") (name "VCC") (class "Default")
      (node (ref "C2") (pin "2") (pinfunction "2_2") (pintype "passive"))
      (node (ref "C4") (pin "2") (pinfunction "2_2") (pintype "passive"))
      (node (ref "C5") (pin "2") (pinfunction "2_2") (pintype "passive"))
      (node (ref "C6") (pin "2") (pinfunction "2_2") (pintype "passive"))
      (node (ref "C7") (pin "2") (pinfunction "2_2") (pintype "passive"))
      (node (ref "LED-CPU") (pin "A") (pinfunction "A_A") (pintype "passive"))
      (node (ref "LED-PWR") (pin "A") (pinfunction "A_A") (pintype "passive"))
      (node (ref "LED-RX") (pin "A") (pinfunction "A_A") (pintype "passive"))
      (node (ref "LED-TX") (pin "A") (pinfunction "A_A") (pintype "passive"))
      (node (ref "PDI-VCC") (pin "P$2") (pinfunction "P1_P$2") (pintype "bidirectional"))
      (node (ref "Q1") (pin "2") (pinfunction "S_2") (pintype "passive"))
      (node (ref "Q2") (pin "2") (pinfunction "S_2") (pintype "passive"))
      (node (ref "Q3") (pin "2") (pinfunction "S_2") (pintype "passive"))
      (node (ref "Q4") (pin "2") (pinfunction "S_2") (pintype "passive"))
      (node (ref "Q5") (pin "2") (pinfunction "S_2") (pintype "passive"))
      (node (ref "Q6") (pin "2") (pinfunction "S_2") (pintype "passive"))
      (node (ref "RN4") (pin "5") (pinfunction "2_5") (pintype "passive"))
      (node (ref "RN4") (pin "6") (pinfunction "2_6") (pintype "passive"))
      (node (ref "RN4") (pin "7") (pinfunction "2_7") (pintype "passive"))
      (node (ref "RN4") (pin "8") (pinfunction "2_8") (pintype "passive"))
      (node (ref "U$1") (pin "COM") (pinfunction "COM_COM") (pintype "bidirectional"))
      (node (ref "U1") (pin "19") (pinfunction "VCC1_19") (pintype "power_in"))
      (node (ref "U1") (pin "31") (pinfunction "VCC2_31") (pintype "power_in"))
      (node (ref "U1") (pin "39") (pinfunction "AVCC_39") (pintype "power_in"))
      (node (ref "U1") (pin "9") (pinfunction "VCC_9") (pintype "power_in"))
      (node (ref "U4") (pin "8") (pinfunction "VCC_8") (pintype "power_in"))
    )
    (net (code "67") (name "unconnected-(U$2-PadNO)") (class "Default")
      (node (ref "U$2") (pin "NO") (pinfunction "NO_NO") (pintype "passive"))
    )
    (net (code "68") (name "unconnected-(U1-PD0-Pad20)") (class "Default")
      (node (ref "U1") (pin "20") (pinfunction "PD0_20") (pintype "bidirectional"))
    )
    (net (code "69") (name "unconnected-(U1-PD1-Pad21)") (class "Default")
      (node (ref "U1") (pin "21") (pinfunction "PD1_21") (pintype "bidirectional"))
    )
    (net (code "70") (name "unconnected-(U1-PD7-Pad27)") (class "Default")
      (node (ref "U1") (pin "27") (pinfunction "PD7_27") (pintype "bidirectional"))
    )
    (net (code "71") (name "unconnected-(U1-PE0-Pad28)") (class "Default")
      (node (ref "U1") (pin "28") (pinfunction "PE0_28") (pintype "bidirectional"))
    )
    (net (code "72") (name "unconnected-(U1-PE1-Pad29)") (class "Default")
      (node (ref "U1") (pin "29") (pinfunction "PE1_29") (pintype "bidirectional"))
    )
    (net (code "73") (name "unconnected-(U1-PE2-Pad32)") (class "Default")
      (node (ref "U1") (pin "32") (pinfunction "PE2_32") (pintype "bidirectional"))
    )
    (net (code "74") (name "unconnected-(U1-PE3-Pad33)") (class "Default")
      (node (ref "U1") (pin "33") (pinfunction "PE3_33") (pintype "bidirectional"))
    )
    (net (code "75") (name "unconnected-(U1-PR0(XT2)-Pad36)") (class "Default")
      (node (ref "U1") (pin "36") (pinfunction "PR0(XT2)_36") (pintype "bidirectional"))
    )
    (net (code "76") (name "unconnected-(U1-PR1(XT1)-Pad37)") (class "Default")
      (node (ref "U1") (pin "37") (pinfunction "PR1(XT1)_37") (pintype "bidirectional"))
    )
    (net (code "77") (name "unconnected-(U2-GP0-Pad2)") (class "Default")
      (node (ref "U2") (pin "2") (pinfunction "GP0_2") (pintype "bidirectional"))
    )
    (net (code "78") (name "unconnected-(U2-GP1-Pad3)") (class "Default")
      (node (ref "U2") (pin "3") (pinfunction "GP1_3") (pintype "bidirectional"))
    )
    (net (code "79") (name "unconnected-(U2-GP2-Pad7)") (class "Default")
      (node (ref "U2") (pin "7") (pinfunction "GP2_7") (pintype "bidirectional"))
    )
    (net (code "80") (name "unconnected-(U2-GP3-Pad8)") (class "Default")
      (node (ref "U2") (pin "8") (pinfunction "GP3_8") (pintype "bidirectional"))
    )
    (net (code "81") (name "unconnected-(U2-SCL-Pad10)") (class "Default")
      (node (ref "U2") (pin "10") (pinfunction "SCL_10") (pintype "output"))
    )
    (net (code "82") (name "unconnected-(U2-SDA-Pad9)") (class "Default")
      (node (ref "U2") (pin "9") (pinfunction "SDA_9") (pintype "bidirectional"))
    )
    (net (code "83") (name "unconnected-(U2-~{RST}-Pad4)") (class "Default")
      (node (ref "U2") (pin "4") (pinfunction "~{RST}_4") (pintype "input"))
    )
    (net (code "84") (name "unconnected-(U3-BYP-Pad4)") (class "Default")
      (node (ref "U3") (pin "4") (pinfunction "BYP_4") (pintype "bidirectional"))
    )
    (net (code "85") (name "unconnected-(USB1B-USBID-PadP4)") (class "Default")
      (node (ref "USB1") (pin "P4") (pinfunction "USBID_P4") (pintype "bidirectional"))
    )
  )
)
